# SwitchBoard_MP3_40.net
KiCad netlist of a schematic drawn in EAGLE
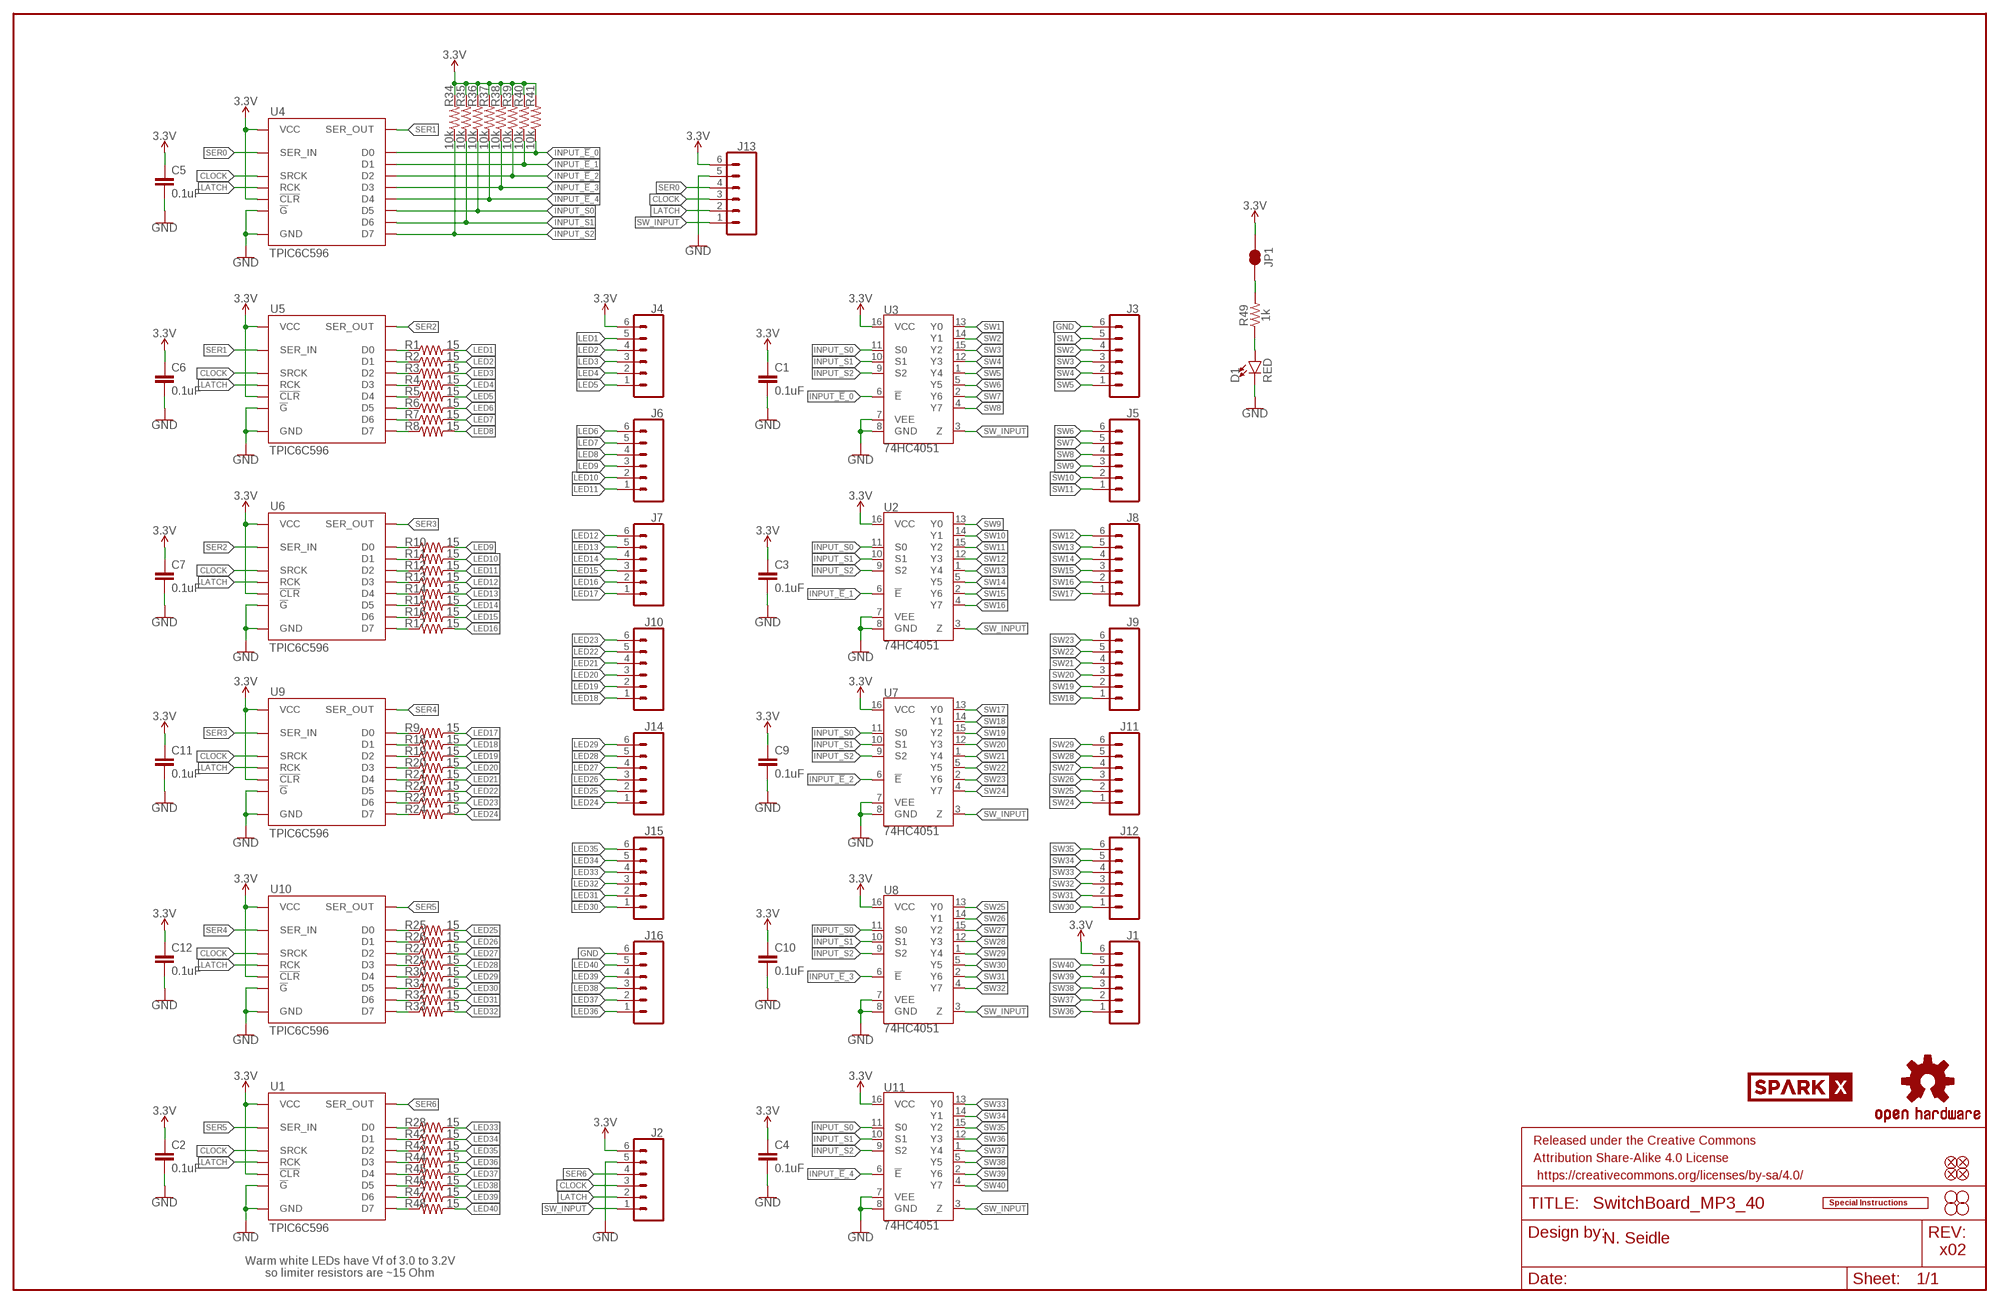
[diagram p0: schematic, sheet 1]

(export (version "E")
  (design (tool "Eeschema 10.0.6"))
  (components
    (comp (ref "C1")
      (value "0.1uF")
      (footprint "eagle-import:0603")
      (libsource (lib "eagle-import") (part "0.1UF-0603-25V-10%-X7R-WE"))
    )
    (comp (ref "C2")
      (value "0.1uF")
      (footprint "eagle-import:0603")
      (libsource (lib "eagle-import") (part "0.1UF-0603-25V-10%-X7R-WE"))
    )
    (comp (ref "C3")
      (value "0.1uF")
      (footprint "eagle-import:0603")
      (libsource (lib "eagle-import") (part "0.1UF-0603-25V-10%-X7R-WE"))
    )
    (comp (ref "C4")
      (value "0.1uF")
      (footprint "eagle-import:0603")
      (libsource (lib "eagle-import") (part "0.1UF-0603-25V-10%-X7R-WE"))
    )
    (comp (ref "C5")
      (value "0.1uF")
      (footprint "eagle-import:0603")
      (libsource (lib "eagle-import") (part "0.1UF-0603-25V-10%-X7R-WE"))
    )
    (comp (ref "C6")
      (value "0.1uF")
      (footprint "eagle-import:0603")
      (libsource (lib "eagle-import") (part "0.1UF-0603-25V-10%-X7R-WE"))
    )
    (comp (ref "C7")
      (value "0.1uF")
      (footprint "eagle-import:0603")
      (libsource (lib "eagle-import") (part "0.1UF-0603-25V-10%-X7R-WE"))
    )
    (comp (ref "C9")
      (value "0.1uF")
      (footprint "eagle-import:0603")
      (libsource (lib "eagle-import") (part "0.1UF-0603-25V-10%-X7R-WE"))
    )
    (comp (ref "C10")
      (value "0.1uF")
      (footprint "eagle-import:0603")
      (libsource (lib "eagle-import") (part "0.1UF-0603-25V-10%-X7R-WE"))
    )
    (comp (ref "C11")
      (value "0.1uF")
      (footprint "eagle-import:0603")
      (libsource (lib "eagle-import") (part "0.1UF-0603-25V-10%-X7R-WE"))
    )
    (comp (ref "C12")
      (value "0.1uF")
      (footprint "eagle-import:0603")
      (libsource (lib "eagle-import") (part "0.1UF-0603-25V-10%-X7R-WE"))
    )
    (comp (ref "D1")
      (value "RED")
      (footprint "eagle-import:LED-0603")
      (libsource (lib "eagle-import") (part "LED-RED0603"))
    )
    (comp (ref "FD1")
      (value "FIDUCIAL1X2")
      (footprint "eagle-import:FIDUCIAL-1X2")
      (libsource (lib "eagle-import") (part "FIDUCIAL1X2"))
    )
    (comp (ref "FD2")
      (value "FIDUCIAL1X2")
      (footprint "eagle-import:FIDUCIAL-1X2")
      (libsource (lib "eagle-import") (part "FIDUCIAL1X2"))
    )
    (comp (ref "FD3")
      (value "FIDUCIAL1X2")
      (footprint "eagle-import:FIDUCIAL-1X2")
      (libsource (lib "eagle-import") (part "FIDUCIAL1X2"))
    )
    (comp (ref "FD4")
      (value "FIDUCIAL1X2")
      (footprint "eagle-import:FIDUCIAL-1X2")
      (libsource (lib "eagle-import") (part "FIDUCIAL1X2"))
    )
    (comp (ref "FRAME2")
      (value "FRAME-LEDGER")
      (footprint "eagle-import:CREATIVE_COMMONS")
      (libsource (lib "eagle-import") (part "FRAME-LEDGER"))
    )
    (comp (ref "H1")
      (value "STAND-OFF")
      (footprint "eagle-import:STAND-OFF")
      (libsource (lib "eagle-import") (part "STAND-OFF"))
    )
    (comp (ref "H2")
      (value "STAND-OFF")
      (footprint "eagle-import:STAND-OFF")
      (libsource (lib "eagle-import") (part "STAND-OFF"))
    )
    (comp (ref "H3")
      (value "STAND-OFF")
      (footprint "eagle-import:STAND-OFF")
      (libsource (lib "eagle-import") (part "STAND-OFF"))
    )
    (comp (ref "H4")
      (value "STAND-OFF")
      (footprint "eagle-import:STAND-OFF")
      (libsource (lib "eagle-import") (part "STAND-OFF"))
    )
    (comp (ref "J1")
      (value "CONN_06JST-SMD-LOCKING")
      (footprint "eagle-import:JST-6-SMD-1.25MM-LOCKING")
      (libsource (lib "eagle-import") (part "CONN_06JST-SMD-LOCKING"))
    )
    (comp (ref "J2")
      (value "CONN_06JST-SMD-LOCKING")
      (footprint "eagle-import:JST-6-SMD-1.25MM-LOCKING")
      (libsource (lib "eagle-import") (part "CONN_06JST-SMD-LOCKING"))
    )
    (comp (ref "J3")
      (value "CONN_06JST-SMD-LOCKING")
      (footprint "eagle-import:JST-6-SMD-1.25MM-LOCKING")
      (libsource (lib "eagle-import") (part "CONN_06JST-SMD-LOCKING"))
    )
    (comp (ref "J4")
      (value "CONN_06JST-SMD-LOCKING")
      (footprint "eagle-import:JST-6-SMD-1.25MM-LOCKING")
      (libsource (lib "eagle-import") (part "CONN_06JST-SMD-LOCKING"))
    )
    (comp (ref "J5")
      (value "CONN_06JST-SMD-LOCKING")
      (footprint "eagle-import:JST-6-SMD-1.25MM-LOCKING")
      (libsource (lib "eagle-import") (part "CONN_06JST-SMD-LOCKING"))
    )
    (comp (ref "J6")
      (value "CONN_06JST-SMD-LOCKING")
      (footprint "eagle-import:JST-6-SMD-1.25MM-LOCKING")
      (libsource (lib "eagle-import") (part "CONN_06JST-SMD-LOCKING"))
    )
    (comp (ref "J7")
      (value "CONN_06JST-SMD-LOCKING")
      (footprint "eagle-import:JST-6-SMD-1.25MM-LOCKING")
      (libsource (lib "eagle-import") (part "CONN_06JST-SMD-LOCKING"))
    )
    (comp (ref "J8")
      (value "CONN_06JST-SMD-LOCKING")
      (footprint "eagle-import:JST-6-SMD-1.25MM-LOCKING")
      (libsource (lib "eagle-import") (part "CONN_06JST-SMD-LOCKING"))
    )
    (comp (ref "J9")
      (value "CONN_06JST-SMD-LOCKING")
      (footprint "eagle-import:JST-6-SMD-1.25MM-LOCKING")
      (libsource (lib "eagle-import") (part "CONN_06JST-SMD-LOCKING"))
    )
    (comp (ref "J10")
      (value "CONN_06JST-SMD-LOCKING")
      (footprint "eagle-import:JST-6-SMD-1.25MM-LOCKING")
      (libsource (lib "eagle-import") (part "CONN_06JST-SMD-LOCKING"))
    )
    (comp (ref "J11")
      (value "CONN_06JST-SMD-LOCKING")
      (footprint "eagle-import:JST-6-SMD-1.25MM-LOCKING")
      (libsource (lib "eagle-import") (part "CONN_06JST-SMD-LOCKING"))
    )
    (comp (ref "J12")
      (value "CONN_06JST-SMD-LOCKING")
      (footprint "eagle-import:JST-6-SMD-1.25MM-LOCKING")
      (libsource (lib "eagle-import") (part "CONN_06JST-SMD-LOCKING"))
    )
    (comp (ref "J13")
      (value "CONN_06JST-SMD-LOCKING")
      (footprint "eagle-import:JST-6-SMD-1.25MM-LOCKING")
      (libsource (lib "eagle-import") (part "CONN_06JST-SMD-LOCKING"))
    )
    (comp (ref "J14")
      (value "CONN_06JST-SMD-LOCKING")
      (footprint "eagle-import:JST-6-SMD-1.25MM-LOCKING")
      (libsource (lib "eagle-import") (part "CONN_06JST-SMD-LOCKING"))
    )
    (comp (ref "J15")
      (value "CONN_06JST-SMD-LOCKING")
      (footprint "eagle-import:JST-6-SMD-1.25MM-LOCKING")
      (libsource (lib "eagle-import") (part "CONN_06JST-SMD-LOCKING"))
    )
    (comp (ref "J16")
      (value "CONN_06JST-SMD-LOCKING")
      (footprint "eagle-import:JST-6-SMD-1.25MM-LOCKING")
      (libsource (lib "eagle-import") (part "CONN_06JST-SMD-LOCKING"))
    )
    (comp (ref "JP1")
      (value "JUMPER-SMT_2_NC_TRACE_SILK")
      (footprint "eagle-import:SMT-JUMPER_2_NC_TRACE_SILK")
      (libsource (lib "eagle-import") (part "JUMPER-SMT_2_NC_TRACE_SILK"))
    )
    (comp (ref "LOGO1")
      (value "SPECIAL_INSTRUCTIONS-ORDERING")
      (footprint "eagle-import:ORDERING_INSTRUCTIONS")
      (libsource (lib "eagle-import") (part "SPECIAL_INSTRUCTIONS-ORDERING"))
    )
    (comp (ref "LOGO2")
      (value "OSHW-LOGOS")
      (footprint "eagle-import:OSHW-LOGO-S")
      (libsource (lib "eagle-import") (part "OSHW-LOGOS"))
    )
    (comp (ref "R1")
      (value "15")
      (footprint "eagle-import:0603")
      (libsource (lib "eagle-import") (part "15OHM-0603-1/10W-1%"))
    )
    (comp (ref "R2")
      (value "15")
      (footprint "eagle-import:0603")
      (libsource (lib "eagle-import") (part "15OHM-0603-1/10W-1%"))
    )
    (comp (ref "R3")
      (value "15")
      (footprint "eagle-import:0603")
      (libsource (lib "eagle-import") (part "15OHM-0603-1/10W-1%"))
    )
    (comp (ref "R4")
      (value "15")
      (footprint "eagle-import:0603")
      (libsource (lib "eagle-import") (part "15OHM-0603-1/10W-1%"))
    )
    (comp (ref "R5")
      (value "15")
      (footprint "eagle-import:0603")
      (libsource (lib "eagle-import") (part "15OHM-0603-1/10W-1%"))
    )
    (comp (ref "R6")
      (value "15")
      (footprint "eagle-import:0603")
      (libsource (lib "eagle-import") (part "15OHM-0603-1/10W-1%"))
    )
    (comp (ref "R7")
      (value "15")
      (footprint "eagle-import:0603")
      (libsource (lib "eagle-import") (part "15OHM-0603-1/10W-1%"))
    )
    (comp (ref "R8")
      (value "15")
      (footprint "eagle-import:0603")
      (libsource (lib "eagle-import") (part "15OHM-0603-1/10W-1%"))
    )
    (comp (ref "R9")
      (value "15")
      (footprint "eagle-import:0603")
      (libsource (lib "eagle-import") (part "15OHM-0603-1/10W-1%"))
    )
    (comp (ref "R10")
      (value "15")
      (footprint "eagle-import:0603")
      (libsource (lib "eagle-import") (part "15OHM-0603-1/10W-1%"))
    )
    (comp (ref "R11")
      (value "15")
      (footprint "eagle-import:0603")
      (libsource (lib "eagle-import") (part "15OHM-0603-1/10W-1%"))
    )
    (comp (ref "R12")
      (value "15")
      (footprint "eagle-import:0603")
      (libsource (lib "eagle-import") (part "15OHM-0603-1/10W-1%"))
    )
    (comp (ref "R13")
      (value "15")
      (footprint "eagle-import:0603")
      (libsource (lib "eagle-import") (part "15OHM-0603-1/10W-1%"))
    )
    (comp (ref "R14")
      (value "15")
      (footprint "eagle-import:0603")
      (libsource (lib "eagle-import") (part "15OHM-0603-1/10W-1%"))
    )
    (comp (ref "R15")
      (value "15")
      (footprint "eagle-import:0603")
      (libsource (lib "eagle-import") (part "15OHM-0603-1/10W-1%"))
    )
    (comp (ref "R16")
      (value "15")
      (footprint "eagle-import:0603")
      (libsource (lib "eagle-import") (part "15OHM-0603-1/10W-1%"))
    )
    (comp (ref "R17")
      (value "15")
      (footprint "eagle-import:0603")
      (libsource (lib "eagle-import") (part "15OHM-0603-1/10W-1%"))
    )
    (comp (ref "R18")
      (value "15")
      (footprint "eagle-import:0603")
      (libsource (lib "eagle-import") (part "15OHM-0603-1/10W-1%"))
    )
    (comp (ref "R19")
      (value "15")
      (footprint "eagle-import:0603")
      (libsource (lib "eagle-import") (part "15OHM-0603-1/10W-1%"))
    )
    (comp (ref "R20")
      (value "15")
      (footprint "eagle-import:0603")
      (libsource (lib "eagle-import") (part "15OHM-0603-1/10W-1%"))
    )
    (comp (ref "R21")
      (value "15")
      (footprint "eagle-import:0603")
      (libsource (lib "eagle-import") (part "15OHM-0603-1/10W-1%"))
    )
    (comp (ref "R22")
      (value "15")
      (footprint "eagle-import:0603")
      (libsource (lib "eagle-import") (part "15OHM-0603-1/10W-1%"))
    )
    (comp (ref "R23")
      (value "15")
      (footprint "eagle-import:0603")
      (libsource (lib "eagle-import") (part "15OHM-0603-1/10W-1%"))
    )
    (comp (ref "R24")
      (value "15")
      (footprint "eagle-import:0603")
      (libsource (lib "eagle-import") (part "15OHM-0603-1/10W-1%"))
    )
    (comp (ref "R25")
      (value "15")
      (footprint "eagle-import:0603")
      (libsource (lib "eagle-import") (part "15OHM-0603-1/10W-1%"))
    )
    (comp (ref "R26")
      (value "15")
      (footprint "eagle-import:0603")
      (libsource (lib "eagle-import") (part "15OHM-0603-1/10W-1%"))
    )
    (comp (ref "R27")
      (value "15")
      (footprint "eagle-import:0603")
      (libsource (lib "eagle-import") (part "15OHM-0603-1/10W-1%"))
    )
    (comp (ref "R28")
      (value "15")
      (footprint "eagle-import:0603")
      (libsource (lib "eagle-import") (part "15OHM-0603-1/10W-1%"))
    )
    (comp (ref "R29")
      (value "15")
      (footprint "eagle-import:0603")
      (libsource (lib "eagle-import") (part "15OHM-0603-1/10W-1%"))
    )
    (comp (ref "R30")
      (value "15")
      (footprint "eagle-import:0603")
      (libsource (lib "eagle-import") (part "15OHM-0603-1/10W-1%"))
    )
    (comp (ref "R31")
      (value "15")
      (footprint "eagle-import:0603")
      (libsource (lib "eagle-import") (part "15OHM-0603-1/10W-1%"))
    )
    (comp (ref "R32")
      (value "15")
      (footprint "eagle-import:0603")
      (libsource (lib "eagle-import") (part "15OHM-0603-1/10W-1%"))
    )
    (comp (ref "R33")
      (value "15")
      (footprint "eagle-import:0603")
      (libsource (lib "eagle-import") (part "15OHM-0603-1/10W-1%"))
    )
    (comp (ref "R34")
      (value "10k")
      (footprint "eagle-import:0603")
      (libsource (lib "eagle-import") (part "10KOHM-0603-1/10W-1%"))
    )
    (comp (ref "R35")
      (value "10k")
      (footprint "eagle-import:0603")
      (libsource (lib "eagle-import") (part "10KOHM-0603-1/10W-1%"))
    )
    (comp (ref "R36")
      (value "10k")
      (footprint "eagle-import:0603")
      (libsource (lib "eagle-import") (part "10KOHM-0603-1/10W-1%"))
    )
    (comp (ref "R37")
      (value "10k")
      (footprint "eagle-import:0603")
      (libsource (lib "eagle-import") (part "10KOHM-0603-1/10W-1%"))
    )
    (comp (ref "R38")
      (value "10k")
      (footprint "eagle-import:0603")
      (libsource (lib "eagle-import") (part "10KOHM-0603-1/10W-1%"))
    )
    (comp (ref "R39")
      (value "10k")
      (footprint "eagle-import:0603")
      (libsource (lib "eagle-import") (part "10KOHM-0603-1/10W-1%"))
    )
    (comp (ref "R40")
      (value "10k")
      (footprint "eagle-import:0603")
      (libsource (lib "eagle-import") (part "10KOHM-0603-1/10W-1%"))
    )
    (comp (ref "R41")
      (value "10k")
      (footprint "eagle-import:0603")
      (libsource (lib "eagle-import") (part "10KOHM-0603-1/10W-1%"))
    )
    (comp (ref "R42")
      (value "15")
      (footprint "eagle-import:0603")
      (libsource (lib "eagle-import") (part "15OHM-0603-1/10W-1%"))
    )
    (comp (ref "R43")
      (value "15")
      (footprint "eagle-import:0603")
      (libsource (lib "eagle-import") (part "15OHM-0603-1/10W-1%"))
    )
    (comp (ref "R44")
      (value "15")
      (footprint "eagle-import:0603")
      (libsource (lib "eagle-import") (part "15OHM-0603-1/10W-1%"))
    )
    (comp (ref "R45")
      (value "15")
      (footprint "eagle-import:0603")
      (libsource (lib "eagle-import") (part "15OHM-0603-1/10W-1%"))
    )
    (comp (ref "R46")
      (value "15")
      (footprint "eagle-import:0603")
      (libsource (lib "eagle-import") (part "15OHM-0603-1/10W-1%"))
    )
    (comp (ref "R47")
      (value "15")
      (footprint "eagle-import:0603")
      (libsource (lib "eagle-import") (part "15OHM-0603-1/10W-1%"))
    )
    (comp (ref "R48")
      (value "15")
      (footprint "eagle-import:0603")
      (libsource (lib "eagle-import") (part "15OHM-0603-1/10W-1%"))
    )
    (comp (ref "R49")
      (value "1k")
      (footprint "eagle-import:0603")
      (libsource (lib "eagle-import") (part "1KOHM-0603-1/10W-1%"))
    )
    (comp (ref "U$1")
      (value "SPARKX-LOGO4")
      (footprint "eagle-import:SPARKX-MEDIUM")
      (libsource (lib "eagle-import") (part "SPARKX-LOGO4"))
    )
    (comp (ref "U1")
      (value "TPIC6C596")
      (footprint "eagle-import:SO016")
      (libsource (lib "eagle-import") (part "TPIC6C596SOIC"))
    )
    (comp (ref "U2")
      (value "74HC4051")
      (footprint "eagle-import:SO16")
      (libsource (lib "eagle-import") (part "744051"))
    )
    (comp (ref "U3")
      (value "74HC4051")
      (footprint "eagle-import:SO16")
      (libsource (lib "eagle-import") (part "744051"))
    )
    (comp (ref "U4")
      (value "TPIC6C596")
      (footprint "eagle-import:SO016")
      (libsource (lib "eagle-import") (part "TPIC6C596SOIC"))
    )
    (comp (ref "U5")
      (value "TPIC6C596")
      (footprint "eagle-import:SO016")
      (libsource (lib "eagle-import") (part "TPIC6C596SOIC"))
    )
    (comp (ref "U6")
      (value "TPIC6C596")
      (footprint "eagle-import:SO016")
      (libsource (lib "eagle-import") (part "TPIC6C596SOIC"))
    )
    (comp (ref "U7")
      (value "74HC4051")
      (footprint "eagle-import:SO16")
      (libsource (lib "eagle-import") (part "744051"))
    )
    (comp (ref "U8")
      (value "74HC4051")
      (footprint "eagle-import:SO16")
      (libsource (lib "eagle-import") (part "744051"))
    )
    (comp (ref "U9")
      (value "TPIC6C596")
      (footprint "eagle-import:SO016")
      (libsource (lib "eagle-import") (part "TPIC6C596SOIC"))
    )
    (comp (ref "U10")
      (value "TPIC6C596")
      (footprint "eagle-import:SO016")
      (libsource (lib "eagle-import") (part "TPIC6C596SOIC"))
    )
    (comp (ref "U11")
      (value "74HC4051")
      (footprint "eagle-import:SO16")
      (libsource (lib "eagle-import") (part "744051"))
    )
  )
  (nets
    (net (code "1") (name "/INPUT_~{E}_0") (class "Default")
      (node (ref "R41") (pin "1") (pinfunction "1_1") (pintype "passive"))
      (node (ref "U3") (pin "6") (pinfunction "~{E}_6") (pintype "bidirectional"))
      (node (ref "U4") (pin "3") (pinfunction "D0_3") (pintype "output"))
    )
    (net (code "2") (name "/INPUT_~{E}_1") (class "Default")
      (node (ref "R40") (pin "1") (pinfunction "1_1") (pintype "passive"))
      (node (ref "U2") (pin "6") (pinfunction "~{E}_6") (pintype "bidirectional"))
      (node (ref "U4") (pin "4") (pinfunction "D1_4") (pintype "output"))
    )
    (net (code "3") (name "/INPUT_~{E}_2") (class "Default")
      (node (ref "R39") (pin "1") (pinfunction "1_1") (pintype "passive"))
      (node (ref "U4") (pin "5") (pinfunction "D2_5") (pintype "output"))
      (node (ref "U7") (pin "6") (pinfunction "~{E}_6") (pintype "bidirectional"))
    )
    (net (code "4") (name "/INPUT_~{E}_3") (class "Default")
      (node (ref "R38") (pin "1") (pinfunction "1_1") (pintype "passive"))
      (node (ref "U4") (pin "6") (pinfunction "D3_6") (pintype "output"))
      (node (ref "U8") (pin "6") (pinfunction "~{E}_6") (pintype "bidirectional"))
    )
    (net (code "5") (name "/INPUT_~{E}_4") (class "Default")
      (node (ref "R37") (pin "1") (pinfunction "1_1") (pintype "passive"))
      (node (ref "U11") (pin "6") (pinfunction "~{E}_6") (pintype "bidirectional"))
      (node (ref "U4") (pin "11") (pinfunction "D4_11") (pintype "output"))
    )
    (net (code "6") (name "3.3V") (class "Default")
      (node (ref "C1") (pin "1") (pinfunction "1_1") (pintype "passive"))
      (node (ref "C10") (pin "1") (pinfunction "1_1") (pintype "passive"))
      (node (ref "C11") (pin "1") (pinfunction "1_1") (pintype "passive"))
      (node (ref "C12") (pin "1") (pinfunction "1_1") (pintype "passive"))
      (node (ref "C2") (pin "1") (pinfunction "1_1") (pintype "passive"))
      (node (ref "C3") (pin "1") (pinfunction "1_1") (pintype "passive"))
      (node (ref "C4") (pin "1") (pinfunction "1_1") (pintype "passive"))
      (node (ref "C5") (pin "1") (pinfunction "1_1") (pintype "passive"))
      (node (ref "C6") (pin "1") (pinfunction "1_1") (pintype "passive"))
      (node (ref "C7") (pin "1") (pinfunction "1_1") (pintype "passive"))
      (node (ref "C9") (pin "1") (pinfunction "1_1") (pintype "passive"))
      (node (ref "J1") (pin "6") (pinfunction "6_6") (pintype "passive"))
      (node (ref "J13") (pin "6") (pinfunction "6_6") (pintype "passive"))
      (node (ref "J2") (pin "6") (pinfunction "6_6") (pintype "passive"))
      (node (ref "J4") (pin "6") (pinfunction "6_6") (pintype "passive"))
      (node (ref "JP1") (pin "2") (pinfunction "2_2") (pintype "passive"))
      (node (ref "R34") (pin "2") (pinfunction "2_2") (pintype "passive"))
      (node (ref "R35") (pin "2") (pinfunction "2_2") (pintype "passive"))
      (node (ref "R36") (pin "2") (pinfunction "2_2") (pintype "passive"))
      (node (ref "R37") (pin "2") (pinfunction "2_2") (pintype "passive"))
      (node (ref "R38") (pin "2") (pinfunction "2_2") (pintype "passive"))
      (node (ref "R39") (pin "2") (pinfunction "2_2") (pintype "passive"))
      (node (ref "R40") (pin "2") (pinfunction "2_2") (pintype "passive"))
      (node (ref "R41") (pin "2") (pinfunction "2_2") (pintype "passive"))
      (node (ref "U1") (pin "1") (pinfunction "VCC_1") (pintype "power_in"))
      (node (ref "U1") (pin "7") (pinfunction "~{CLR}_7") (pintype "input"))
      (node (ref "U10") (pin "1") (pinfunction "VCC_1") (pintype "power_in"))
      (node (ref "U10") (pin "7") (pinfunction "~{CLR}_7") (pintype "input"))
      (node (ref "U11") (pin "16") (pinfunction "VCC_16") (pintype "bidirectional"))
      (node (ref "U2") (pin "16") (pinfunction "VCC_16") (pintype "bidirectional"))
      (node (ref "U3") (pin "16") (pinfunction "VCC_16") (pintype "bidirectional"))
      (node (ref "U4") (pin "1") (pinfunction "VCC_1") (pintype "power_in"))
      (node (ref "U4") (pin "7") (pinfunction "~{CLR}_7") (pintype "input"))
      (node (ref "U5") (pin "1") (pinfunction "VCC_1") (pintype "power_in"))
      (node (ref "U5") (pin "7") (pinfunction "~{CLR}_7") (pintype "input"))
      (node (ref "U6") (pin "1") (pinfunction "VCC_1") (pintype "power_in"))
      (node (ref "U6") (pin "7") (pinfunction "~{CLR}_7") (pintype "input"))
      (node (ref "U7") (pin "16") (pinfunction "VCC_16") (pintype "bidirectional"))
      (node (ref "U8") (pin "16") (pinfunction "VCC_16") (pintype "bidirectional"))
      (node (ref "U9") (pin "1") (pinfunction "VCC_1") (pintype "power_in"))
      (node (ref "U9") (pin "7") (pinfunction "~{CLR}_7") (pintype "input"))
    )
    (net (code "7") (name "CLOCK") (class "Default")
      (node (ref "J13") (pin "3") (pinfunction "3_3") (pintype "passive"))
      (node (ref "J2") (pin "3") (pinfunction "3_3") (pintype "passive"))
      (node (ref "U1") (pin "15") (pinfunction "SRCK_15") (pintype "input"))
      (node (ref "U10") (pin "15") (pinfunction "SRCK_15") (pintype "input"))
      (node (ref "U4") (pin "15") (pinfunction "SRCK_15") (pintype "input"))
      (node (ref "U5") (pin "15") (pinfunction "SRCK_15") (pintype "input"))
      (node (ref "U6") (pin "15") (pinfunction "SRCK_15") (pintype "input"))
      (node (ref "U9") (pin "15") (pinfunction "SRCK_15") (pintype "input"))
    )
    (net (code "8") (name "GND") (class "Default")
      (node (ref "C1") (pin "2") (pinfunction "2_2") (pintype "passive"))
      (node (ref "C10") (pin "2") (pinfunction "2_2") (pintype "passive"))
      (node (ref "C11") (pin "2") (pinfunction "2_2") (pintype "passive"))
      (node (ref "C12") (pin "2") (pinfunction "2_2") (pintype "passive"))
      (node (ref "C2") (pin "2") (pinfunction "2_2") (pintype "passive"))
      (node (ref "C3") (pin "2") (pinfunction "2_2") (pintype "passive"))
      (node (ref "C4") (pin "2") (pinfunction "2_2") (pintype "passive"))
      (node (ref "C5") (pin "2") (pinfunction "2_2") (pintype "passive"))
      (node (ref "C6") (pin "2") (pinfunction "2_2") (pintype "passive"))
      (node (ref "C7") (pin "2") (pinfunction "2_2") (pintype "passive"))
      (node (ref "C9") (pin "2") (pinfunction "2_2") (pintype "passive"))
      (node (ref "D1") (pin "C") (pinfunction "C_C") (pintype "passive"))
      (node (ref "J13") (pin "5") (pinfunction "5_5") (pintype "passive"))
      (node (ref "J16") (pin "6") (pinfunction "6_6") (pintype "passive"))
      (node (ref "J2") (pin "5") (pinfunction "5_5") (pintype "passive"))
      (node (ref "J3") (pin "6") (pinfunction "6_6") (pintype "passive"))
      (node (ref "U1") (pin "16") (pinfunction "GND_16") (pintype "power_in"))
      (node (ref "U1") (pin "8") (pinfunction "~{G}_8") (pintype "input"))
      (node (ref "U10") (pin "16") (pinfunction "GND_16") (pintype "power_in"))
      (node (ref "U10") (pin "8") (pinfunction "~{G}_8") (pintype "input"))
      (node (ref "U11") (pin "7") (pinfunction "VEE_7") (pintype "bidirectional"))
      (node (ref "U11") (pin "8") (pinfunction "GND_8") (pintype "bidirectional"))
      (node (ref "U2") (pin "7") (pinfunction "VEE_7") (pintype "bidirectional"))
      (node (ref "U2") (pin "8") (pinfunction "GND_8") (pintype "bidirectional"))
      (node (ref "U3") (pin "7") (pinfunction "VEE_7") (pintype "bidirectional"))
      (node (ref "U3") (pin "8") (pinfunction "GND_8") (pintype "bidirectional"))
      (node (ref "U4") (pin "16") (pinfunction "GND_16") (pintype "power_in"))
      (node (ref "U4") (pin "8") (pinfunction "~{G}_8") (pintype "input"))
      (node (ref "U5") (pin "16") (pinfunction "GND_16") (pintype "power_in"))
      (node (ref "U5") (pin "8") (pinfunction "~{G}_8") (pintype "input"))
      (node (ref "U6") (pin "16") (pinfunction "GND_16") (pintype "power_in"))
      (node (ref "U6") (pin "8") (pinfunction "~{G}_8") (pintype "input"))
      (node (ref "U7") (pin "7") (pinfunction "VEE_7") (pintype "bidirectional"))
      (node (ref "U7") (pin "8") (pinfunction "GND_8") (pintype "bidirectional"))
      (node (ref "U8") (pin "7") (pinfunction "VEE_7") (pintype "bidirectional"))
      (node (ref "U8") (pin "8") (pinfunction "GND_8") (pintype "bidirectional"))
      (node (ref "U9") (pin "16") (pinfunction "GND_16") (pintype "power_in"))
      (node (ref "U9") (pin "8") (pinfunction "~{G}_8") (pintype "input"))
    )
    (net (code "9") (name "INPUT_S0") (class "Default")
      (node (ref "R36") (pin "1") (pinfunction "1_1") (pintype "passive"))
      (node (ref "U11") (pin "11") (pinfunction "S0_11") (pintype "bidirectional"))
      (node (ref "U2") (pin "11") (pinfunction "S0_11") (pintype "bidirectional"))
      (node (ref "U3") (pin "11") (pinfunction "S0_11") (pintype "bidirectional"))
      (node (ref "U4") (pin "12") (pinfunction "D5_12") (pintype "output"))
      (node (ref "U7") (pin "11") (pinfunction "S0_11") (pintype "bidirectional"))
      (node (ref "U8") (pin "11") (pinfunction "S0_11") (pintype "bidirectional"))
    )
    (net (code "10") (name "INPUT_S1") (class "Default")
      (node (ref "R35") (pin "1") (pinfunction "1_1") (pintype "passive"))
      (node (ref "U11") (pin "10") (pinfunction "S1_10") (pintype "bidirectional"))
      (node (ref "U2") (pin "10") (pinfunction "S1_10") (pintype "bidirectional"))
      (node (ref "U3") (pin "10") (pinfunction "S1_10") (pintype "bidirectional"))
      (node (ref "U4") (pin "13") (pinfunction "D6_13") (pintype "output"))
      (node (ref "U7") (pin "10") (pinfunction "S1_10") (pintype "bidirectional"))
      (node (ref "U8") (pin "10") (pinfunction "S1_10") (pintype "bidirectional"))
    )
    (net (code "11") (name "INPUT_S2") (class "Default")
      (node (ref "R34") (pin "1") (pinfunction "1_1") (pintype "passive"))
      (node (ref "U11") (pin "9") (pinfunction "S2_9") (pintype "bidirectional"))
      (node (ref "U2") (pin "9") (pinfunction "S2_9") (pintype "bidirectional"))
      (node (ref "U3") (pin "9") (pinfunction "S2_9") (pintype "bidirectional"))
      (node (ref "U4") (pin "14") (pinfunction "D7_14") (pintype "output"))
      (node (ref "U7") (pin "9") (pinfunction "S2_9") (pintype "bidirectional"))
      (node (ref "U8") (pin "9") (pinfunction "S2_9") (pintype "bidirectional"))
    )
    (net (code "12") (name "LATCH") (class "Default")
      (node (ref "J13") (pin "2") (pinfunction "2_2") (pintype "passive"))
      (node (ref "J2") (pin "2") (pinfunction "2_2") (pintype "passive"))
      (node (ref "U1") (pin "10") (pinfunction "RCK_10") (pintype "input"))
      (node (ref "U10") (pin "10") (pinfunction "RCK_10") (pintype "input"))
      (node (ref "U4") (pin "10") (pinfunction "RCK_10") (pintype "input"))
      (node (ref "U5") (pin "10") (pinfunction "RCK_10") (pintype "input"))
      (node (ref "U6") (pin "10") (pinfunction "RCK_10") (pintype "input"))
      (node (ref "U9") (pin "10") (pinfunction "RCK_10") (pintype "input"))
    )
    (net (code "13") (name "LED1") (class "Default")
      (node (ref "J4") (pin "5") (pinfunction "5_5") (pintype "passive"))
      (node (ref "R1") (pin "2") (pinfunction "2_2") (pintype "passive"))
    )
    (net (code "14") (name "LED2") (class "Default")
      (node (ref "J4") (pin "4") (pinfunction "4_4") (pintype "passive"))
      (node (ref "R2") (pin "2") (pinfunction "2_2") (pintype "passive"))
    )
    (net (code "15") (name "LED3") (class "Default")
      (node (ref "J4") (pin "3") (pinfunction "3_3") (pintype "passive"))
      (node (ref "R3") (pin "2") (pinfunction "2_2") (pintype "passive"))
    )
    (net (code "16") (name "LED4") (class "Default")
      (node (ref "J4") (pin "2") (pinfunction "2_2") (pintype "passive"))
      (node (ref "R4") (pin "2") (pinfunction "2_2") (pintype "passive"))
    )
    (net (code "17") (name "LED5") (class "Default")
      (node (ref "J4") (pin "1") (pinfunction "1_1") (pintype "passive"))
      (node (ref "R5") (pin "2") (pinfunction "2_2") (pintype "passive"))
    )
    (net (code "18") (name "LED6") (class "Default")
      (node (ref "J6") (pin "6") (pinfunction "6_6") (pintype "passive"))
      (node (ref "R6") (pin "2") (pinfunction "2_2") (pintype "passive"))
    )
    (net (code "19") (name "LED7") (class "Default")
      (node (ref "J6") (pin "5") (pinfunction "5_5") (pintype "passive"))
      (node (ref "R7") (pin "2") (pinfunction "2_2") (pintype "passive"))
    )
    (net (code "20") (name "LED8") (class "Default")
      (node (ref "J6") (pin "4") (pinfunction "4_4") (pintype "passive"))
      (node (ref "R8") (pin "2") (pinfunction "2_2") (pintype "passive"))
    )
    (net (code "21") (name "LED9") (class "Default")
      (node (ref "J6") (pin "3") (pinfunction "3_3") (pintype "passive"))
      (node (ref "R10") (pin "2") (pinfunction "2_2") (pintype "passive"))
    )
    (net (code "22") (name "LED10") (class "Default")
      (node (ref "J6") (pin "2") (pinfunction "2_2") (pintype "passive"))
      (node (ref "R11") (pin "2") (pinfunction "2_2") (pintype "passive"))
    )
    (net (code "23") (name "LED11") (class "Default")
      (node (ref "J6") (pin "1") (pinfunction "1_1") (pintype "passive"))
      (node (ref "R12") (pin "2") (pinfunction "2_2") (pintype "passive"))
    )
    (net (code "24") (name "LED12") (class "Default")
      (node (ref "J7") (pin "6") (pinfunction "6_6") (pintype "passive"))
      (node (ref "R13") (pin "2") (pinfunction "2_2") (pintype "passive"))
    )
    (net (code "25") (name "LED13") (class "Default")
      (node (ref "J7") (pin "5") (pinfunction "5_5") (pintype "passive"))
      (node (ref "R14") (pin "2") (pinfunction "2_2") (pintype "passive"))
    )
    (net (code "26") (name "LED14") (class "Default")
      (node (ref "J7") (pin "4") (pinfunction "4_4") (pintype "passive"))
      (node (ref "R15") (pin "2") (pinfunction "2_2") (pintype "passive"))
    )
    (net (code "27") (name "LED15") (class "Default")
      (node (ref "J7") (pin "3") (pinfunction "3_3") (pintype "passive"))
      (node (ref "R16") (pin "2") (pinfunction "2_2") (pintype "passive"))
    )
    (net (code "28") (name "LED16") (class "Default")
      (node (ref "J7") (pin "2") (pinfunction "2_2") (pintype "passive"))
      (node (ref "R17") (pin "2") (pinfunction "2_2") (pintype "passive"))
    )
    (net (code "29") (name "LED17") (class "Default")
      (node (ref "J7") (pin "1") (pinfunction "1_1") (pintype "passive"))
      (node (ref "R9") (pin "2") (pinfunction "2_2") (pintype "passive"))
    )
    (net (code "30") (name "LED18") (class "Default")
      (node (ref "J10") (pin "1") (pinfunction "1_1") (pintype "passive"))
      (node (ref "R18") (pin "2") (pinfunction "2_2") (pintype "passive"))
    )
    (net (code "31") (name "LED19") (class "Default")
      (node (ref "J10") (pin "2") (pinfunction "2_2") (pintype "passive"))
      (node (ref "R19") (pin "2") (pinfunction "2_2") (pintype "passive"))
    )
    (net (code "32") (name "LED20") (class "Default")
      (node (ref "J10") (pin "3") (pinfunction "3_3") (pintype "passive"))
      (node (ref "R20") (pin "2") (pinfunction "2_2") (pintype "passive"))
    )
    (net (code "33") (name "LED21") (class "Default")
      (node (ref "J10") (pin "4") (pinfunction "4_4") (pintype "passive"))
      (node (ref "R21") (pin "2") (pinfunction "2_2") (pintype "passive"))
    )
    (net (code "34") (name "LED22") (class "Default")
      (node (ref "J10") (pin "5") (pinfunction "5_5") (pintype "passive"))
      (node (ref "R22") (pin "2") (pinfunction "2_2") (pintype "passive"))
    )
    (net (code "35") (name "LED23") (class "Default")
      (node (ref "J10") (pin "6") (pinfunction "6_6") (pintype "passive"))
      (node (ref "R23") (pin "2") (pinfunction "2_2") (pintype "passive"))
    )
    (net (code "36") (name "LED24") (class "Default")
      (node (ref "J14") (pin "1") (pinfunction "1_1") (pintype "passive"))
      (node (ref "R24") (pin "2") (pinfunction "2_2") (pintype "passive"))
    )
    (net (code "37") (name "LED25") (class "Default")
      (node (ref "J14") (pin "2") (pinfunction "2_2") (pintype "passive"))
      (node (ref "R25") (pin "2") (pinfunction "2_2") (pintype "passive"))
    )
    (net (code "38") (name "LED26") (class "Default")
      (node (ref "J14") (pin "3") (pinfunction "3_3") (pintype "passive"))
      (node (ref "R26") (pin "2") (pinfunction "2_2") (pintype "passive"))
    )
    (net (code "39") (name "LED27") (class "Default")
      (node (ref "J14") (pin "4") (pinfunction "4_4") (pintype "passive"))
      (node (ref "R27") (pin "2") (pinfunction "2_2") (pintype "passive"))
    )
    (net (code "40") (name "LED28") (class "Default")
      (node (ref "J14") (pin "5") (pinfunction "5_5") (pintype "passive"))
      (node (ref "R29") (pin "2") (pinfunction "2_2") (pintype "passive"))
    )
    (net (code "41") (name "LED29") (class "Default")
      (node (ref "J14") (pin "6") (pinfunction "6_6") (pintype "passive"))
      (node (ref "R30") (pin "2") (pinfunction "2_2") (pintype "passive"))
    )
    (net (code "42") (name "LED30") (class "Default")
      (node (ref "J15") (pin "1") (pinfunction "1_1") (pintype "passive"))
      (node (ref "R31") (pin "2") (pinfunction "2_2") (pintype "passive"))
    )
    (net (code "43") (name "LED31") (class "Default")
      (node (ref "J15") (pin "2") (pinfunction "2_2") (pintype "passive"))
      (node (ref "R32") (pin "2") (pinfunction "2_2") (pintype "passive"))
    )
    (net (code "44") (name "LED32") (class "Default")
      (node (ref "J15") (pin "3") (pinfunction "3_3") (pintype "passive"))
      (node (ref "R33") (pin "2") (pinfunction "2_2") (pintype "passive"))
    )
    (net (code "45") (name "LED33") (class "Default")
      (node (ref "J15") (pin "4") (pinfunction "4_4") (pintype "passive"))
      (node (ref "R28") (pin "2") (pinfunction "2_2") (pintype "passive"))
    )
    (net (code "46") (name "LED34") (class "Default")
      (node (ref "J15") (pin "5") (pinfunction "5_5") (pintype "passive"))
      (node (ref "R42") (pin "2") (pinfunction "2_2") (pintype "passive"))
    )
    (net (code "47") (name "LED35") (class "Default")
      (node (ref "J15") (pin "6") (pinfunction "6_6") (pintype "passive"))
      (node (ref "R43") (pin "2") (pinfunction "2_2") (pintype "passive"))
    )
    (net (code "48") (name "LED36") (class "Default")
      (node (ref "J16") (pin "1") (pinfunction "1_1") (pintype "passive"))
      (node (ref "R44") (pin "2") (pinfunction "2_2") (pintype "passive"))
    )
    (net (code "49") (name "LED37") (class "Default")
      (node (ref "J16") (pin "2") (pinfunction "2_2") (pintype "passive"))
      (node (ref "R45") (pin "2") (pinfunction "2_2") (pintype "passive"))
    )
    (net (code "50") (name "LED38") (class "Default")
      (node (ref "J16") (pin "3") (pinfunction "3_3") (pintype "passive"))
      (node (ref "R46") (pin "2") (pinfunction "2_2") (pintype "passive"))
    )
    (net (code "51") (name "LED39") (class "Default")
      (node (ref "J16") (pin "4") (pinfunction "4_4") (pintype "passive"))
      (node (ref "R47") (pin "2") (pinfunction "2_2") (pintype "passive"))
    )
    (net (code "52") (name "LED40") (class "Default")
      (node (ref "J16") (pin "5") (pinfunction "5_5") (pintype "passive"))
      (node (ref "R48") (pin "2") (pinfunction "2_2") (pintype "passive"))
    )
    (net (code "53") (name "Net-(D1-PadA)") (class "Default")
      (node (ref "D1") (pin "A") (pinfunction "A_A") (pintype "passive"))
      (node (ref "R49") (pin "1") (pinfunction "1_1") (pintype "passive"))
    )
    (net (code "54") (name "Net-(JP1-Pad1)") (class "Default")
      (node (ref "JP1") (pin "1") (pinfunction "1_1") (pintype "passive"))
      (node (ref "R49") (pin "2") (pinfunction "2_2") (pintype "passive"))
    )
    (net (code "55") (name "Net-(U1-D0)") (class "Default")
      (node (ref "R28") (pin "1") (pinfunction "1_1") (pintype "passive"))
      (node (ref "U1") (pin "3") (pinfunction "D0_3") (pintype "output"))
    )
    (net (code "56") (name "Net-(U1-D1)") (class "Default")
      (node (ref "R42") (pin "1") (pinfunction "1_1") (pintype "passive"))
      (node (ref "U1") (pin "4") (pinfunction "D1_4") (pintype "output"))
    )
    (net (code "57") (name "Net-(U1-D2)") (class "Default")
      (node (ref "R43") (pin "1") (pinfunction "1_1") (pintype "passive"))
      (node (ref "U1") (pin "5") (pinfunction "D2_5") (pintype "output"))
    )
    (net (code "58") (name "Net-(U1-D3)") (class "Default")
      (node (ref "R44") (pin "1") (pinfunction "1_1") (pintype "passive"))
      (node (ref "U1") (pin "6") (pinfunction "D3_6") (pintype "output"))
    )
    (net (code "59") (name "Net-(U1-D4)") (class "Default")
      (node (ref "R45") (pin "1") (pinfunction "1_1") (pintype "passive"))
      (node (ref "U1") (pin "11") (pinfunction "D4_11") (pintype "output"))
    )
    (net (code "60") (name "Net-(U1-D5)") (class "Default")
      (node (ref "R46") (pin "1") (pinfunction "1_1") (pintype "passive"))
      (node (ref "U1") (pin "12") (pinfunction "D5_12") (pintype "output"))
    )
    (net (code "61") (name "Net-(U1-D6)") (class "Default")
      (node (ref "R47") (pin "1") (pinfunction "1_1") (pintype "passive"))
      (node (ref "U1") (pin "13") (pinfunction "D6_13") (pintype "output"))
    )
    (net (code "62") (name "Net-(U1-D7)") (class "Default")
      (node (ref "R48") (pin "1") (pinfunction "1_1") (pintype "passive"))
      (node (ref "U1") (pin "14") (pinfunction "D7_14") (pintype "output"))
    )
    (net (code "63") (name "Net-(U5-D0)") (class "Default")
      (node (ref "R1") (pin "1") (pinfunction "1_1") (pintype "passive"))
      (node (ref "U5") (pin "3") (pinfunction "D0_3") (pintype "output"))
    )
    (net (code "64") (name "Net-(U5-D1)") (class "Default")
      (node (ref "R2") (pin "1") (pinfunction "1_1") (pintype "passive"))
      (node (ref "U5") (pin "4") (pinfunction "D1_4") (pintype "output"))
    )
    (net (code "65") (name "Net-(U5-D2)") (class "Default")
      (node (ref "R3") (pin "1") (pinfunction "1_1") (pintype "passive"))
      (node (ref "U5") (pin "5") (pinfunction "D2_5") (pintype "output"))
    )
    (net (code "66") (name "Net-(U5-D3)") (class "Default")
      (node (ref "R4") (pin "1") (pinfunction "1_1") (pintype "passive"))
      (node (ref "U5") (pin "6") (pinfunction "D3_6") (pintype "output"))
    )
    (net (code "67") (name "Net-(U5-D4)") (class "Default")
      (node (ref "R5") (pin "1") (pinfunction "1_1") (pintype "passive"))
      (node (ref "U5") (pin "11") (pinfunction "D4_11") (pintype "output"))
    )
    (net (code "68") (name "Net-(U5-D5)") (class "Default")
      (node (ref "R6") (pin "1") (pinfunction "1_1") (pintype "passive"))
      (node (ref "U5") (pin "12") (pinfunction "D5_12") (pintype "output"))
    )
    (net (code "69") (name "Net-(U5-D6)") (class "Default")
      (node (ref "R7") (pin "1") (pinfunction "1_1") (pintype "passive"))
      (node (ref "U5") (pin "13") (pinfunction "D6_13") (pintype "output"))
    )
    (net (code "70") (name "Net-(U5-D7)") (class "Default")
      (node (ref "R8") (pin "1") (pinfunction "1_1") (pintype "passive"))
      (node (ref "U5") (pin "14") (pinfunction "D7_14") (pintype "output"))
    )
    (net (code "71") (name "Net-(U6-D0)") (class "Default")
      (node (ref "R10") (pin "1") (pinfunction "1_1") (pintype "passive"))
      (node (ref "U6") (pin "3") (pinfunction "D0_3") (pintype "output"))
    )
    (net (code "72") (name "Net-(U6-D1)") (class "Default")
      (node (ref "R11") (pin "1") (pinfunction "1_1") (pintype "passive"))
      (node (ref "U6") (pin "4") (pinfunction "D1_4") (pintype "output"))
    )
    (net (code "73") (name "Net-(U6-D2)") (class "Default")
      (node (ref "R12") (pin "1") (pinfunction "1_1") (pintype "passive"))
      (node (ref "U6") (pin "5") (pinfunction "D2_5") (pintype "output"))
    )
    (net (code "74") (name "Net-(U6-D3)") (class "Default")
      (node (ref "R13") (pin "1") (pinfunction "1_1") (pintype "passive"))
      (node (ref "U6") (pin "6") (pinfunction "D3_6") (pintype "output"))
    )
    (net (code "75") (name "Net-(U6-D4)") (class "Default")
      (node (ref "R14") (pin "1") (pinfunction "1_1") (pintype "passive"))
      (node (ref "U6") (pin "11") (pinfunction "D4_11") (pintype "output"))
    )
    (net (code "76") (name "Net-(U6-D5)") (class "Default")
      (node (ref "R15") (pin "1") (pinfunction "1_1") (pintype "passive"))
      (node (ref "U6") (pin "12") (pinfunction "D5_12") (pintype "output"))
    )
    (net (code "77") (name "Net-(U6-D6)") (class "Default")
      (node (ref "R16") (pin "1") (pinfunction "1_1") (pintype "passive"))
      (node (ref "U6") (pin "13") (pinfunction "D6_13") (pintype "output"))
    )
    (net (code "78") (name "Net-(U6-D7)") (class "Default")
      (node (ref "R17") (pin "1") (pinfunction "1_1") (pintype "passive"))
      (node (ref "U6") (pin "14") (pinfunction "D7_14") (pintype "output"))
    )
    (net (code "79") (name "Net-(U9-D0)") (class "Default")
      (node (ref "R9") (pin "1") (pinfunction "1_1") (pintype "passive"))
      (node (ref "U9") (pin "3") (pinfunction "D0_3") (pintype "output"))
    )
    (net (code "80") (name "Net-(U9-D1)") (class "Default")
      (node (ref "R18") (pin "1") (pinfunction "1_1") (pintype "passive"))
      (node (ref "U9") (pin "4") (pinfunction "D1_4") (pintype "output"))
    )
    (net (code "81") (name "Net-(U9-D2)") (class "Default")
      (node (ref "R19") (pin "1") (pinfunction "1_1") (pintype "passive"))
      (node (ref "U9") (pin "5") (pinfunction "D2_5") (pintype "output"))
    )
    (net (code "82") (name "Net-(U9-D3)") (class "Default")
      (node (ref "R20") (pin "1") (pinfunction "1_1") (pintype "passive"))
      (node (ref "U9") (pin "6") (pinfunction "D3_6") (pintype "output"))
    )
    (net (code "83") (name "Net-(U9-D4)") (class "Default")
      (node (ref "R21") (pin "1") (pinfunction "1_1") (pintype "passive"))
      (node (ref "U9") (pin "11") (pinfunction "D4_11") (pintype "output"))
    )
    (net (code "84") (name "Net-(U9-D5)") (class "Default")
      (node (ref "R22") (pin "1") (pinfunction "1_1") (pintype "passive"))
      (node (ref "U9") (pin "12") (pinfunction "D5_12") (pintype "output"))
    )
    (net (code "85") (name "Net-(U9-D6)") (class "Default")
      (node (ref "R23") (pin "1") (pinfunction "1_1") (pintype "passive"))
      (node (ref "U9") (pin "13") (pinfunction "D6_13") (pintype "output"))
    )
    (net (code "86") (name "Net-(U9-D7)") (class "Default")
      (node (ref "R24") (pin "1") (pinfunction "1_1") (pintype "passive"))
      (node (ref "U9") (pin "14") (pinfunction "D7_14") (pintype "output"))
    )
    (net (code "87") (name "Net-(U10-D0)") (class "Default")
      (node (ref "R25") (pin "1") (pinfunction "1_1") (pintype "passive"))
      (node (ref "U10") (pin "3") (pinfunction "D0_3") (pintype "output"))
    )
    (net (code "88") (name "Net-(U10-D1)") (class "Default")
      (node (ref "R26") (pin "1") (pinfunction "1_1") (pintype "passive"))
      (node (ref "U10") (pin "4") (pinfunction "D1_4") (pintype "output"))
    )
    (net (code "89") (name "Net-(U10-D2)") (class "Default")
      (node (ref "R27") (pin "1") (pinfunction "1_1") (pintype "passive"))
      (node (ref "U10") (pin "5") (pinfunction "D2_5") (pintype "output"))
    )
    (net (code "90") (name "Net-(U10-D3)") (class "Default")
      (node (ref "R29") (pin "1") (pinfunction "1_1") (pintype "passive"))
      (node (ref "U10") (pin "6") (pinfunction "D3_6") (pintype "output"))
    )
    (net (code "91") (name "Net-(U10-D4)") (class "Default")
      (node (ref "R30") (pin "1") (pinfunction "1_1") (pintype "passive"))
      (node (ref "U10") (pin "11") (pinfunction "D4_11") (pintype "output"))
    )
    (net (code "92") (name "Net-(U10-D5)") (class "Default")
      (node (ref "R31") (pin "1") (pinfunction "1_1") (pintype "passive"))
      (node (ref "U10") (pin "12") (pinfunction "D5_12") (pintype "output"))
    )
    (net (code "93") (name "Net-(U10-D6)") (class "Default")
      (node (ref "R32") (pin "1") (pinfunction "1_1") (pintype "passive"))
      (node (ref "U10") (pin "13") (pinfunction "D6_13") (pintype "output"))
    )
    (net (code "94") (name "Net-(U10-D7)") (class "Default")
      (node (ref "R33") (pin "1") (pinfunction "1_1") (pintype "passive"))
      (node (ref "U10") (pin "14") (pinfunction "D7_14") (pintype "output"))
    )
    (net (code "95") (name "SER0") (class "Default")
      (node (ref "J13") (pin "4") (pinfunction "4_4") (pintype "passive"))
      (node (ref "U4") (pin "2") (pinfunction "SER_IN_2") (pintype "input"))
    )
    (net (code "96") (name "SER1") (class "Default")
      (node (ref "U4") (pin "9") (pinfunction "SER_OUT_9") (pintype "output"))
      (node (ref "U5") (pin "2") (pinfunction "SER_IN_2") (pintype "input"))
    )
    (net (code "97") (name "SER2") (class "Default")
      (node (ref "U5") (pin "9") (pinfunction "SER_OUT_9") (pintype "output"))
      (node (ref "U6") (pin "2") (pinfunction "SER_IN_2") (pintype "input"))
    )
    (net (code "98") (name "SER3") (class "Default")
      (node (ref "U6") (pin "9") (pinfunction "SER_OUT_9") (pintype "output"))
      (node (ref "U9") (pin "2") (pinfunction "SER_IN_2") (pintype "input"))
    )
    (net (code "99") (name "SER4") (class "Default")
      (node (ref "U10") (pin "2") (pinfunction "SER_IN_2") (pintype "input"))
      (node (ref "U9") (pin "9") (pinfunction "SER_OUT_9") (pintype "output"))
    )
    (net (code "100") (name "SER5") (class "Default")
      (node (ref "U1") (pin "2") (pinfunction "SER_IN_2") (pintype "input"))
      (node (ref "U10") (pin "9") (pinfunction "SER_OUT_9") (pintype "output"))
    )
    (net (code "101") (name "SER6") (class "Default")
      (node (ref "J2") (pin "4") (pinfunction "4_4") (pintype "passive"))
      (node (ref "U1") (pin "9") (pinfunction "SER_OUT_9") (pintype "output"))
    )
    (net (code "102") (name "SW1") (class "Default")
      (node (ref "J3") (pin "5") (pinfunction "5_5") (pintype "passive"))
      (node (ref "U3") (pin "13") (pinfunction "Y0_13") (pintype "bidirectional"))
    )
    (net (code "103") (name "SW2") (class "Default")
      (node (ref "J3") (pin "4") (pinfunction "4_4") (pintype "passive"))
      (node (ref "U3") (pin "14") (pinfunction "Y1_14") (pintype "bidirectional"))
    )
    (net (code "104") (name "SW3") (class "Default")
      (node (ref "J3") (pin "3") (pinfunction "3_3") (pintype "passive"))
      (node (ref "U3") (pin "15") (pinfunction "Y2_15") (pintype "bidirectional"))
    )
    (net (code "105") (name "SW4") (class "Default")
      (node (ref "J3") (pin "2") (pinfunction "2_2") (pintype "passive"))
      (node (ref "U3") (pin "12") (pinfunction "Y3_12") (pintype "bidirectional"))
    )
    (net (code "106") (name "SW5") (class "Default")
      (node (ref "J3") (pin "1") (pinfunction "1_1") (pintype "passive"))
      (node (ref "U3") (pin "1") (pinfunction "Y4_1") (pintype "bidirectional"))
    )
    (net (code "107") (name "SW6") (class "Default")
      (node (ref "J5") (pin "6") (pinfunction "6_6") (pintype "passive"))
      (node (ref "U3") (pin "5") (pinfunction "Y5_5") (pintype "bidirectional"))
    )
    (net (code "108") (name "SW7") (class "Default")
      (node (ref "J5") (pin "5") (pinfunction "5_5") (pintype "passive"))
      (node (ref "U3") (pin "2") (pinfunction "Y6_2") (pintype "bidirectional"))
    )
    (net (code "109") (name "SW8") (class "Default")
      (node (ref "J5") (pin "4") (pinfunction "4_4") (pintype "passive"))
      (node (ref "U3") (pin "4") (pinfunction "Y7_4") (pintype "bidirectional"))
    )
    (net (code "110") (name "SW9") (class "Default")
      (node (ref "J5") (pin "3") (pinfunction "3_3") (pintype "passive"))
      (node (ref "U2") (pin "13") (pinfunction "Y0_13") (pintype "bidirectional"))
    )
    (net (code "111") (name "SW10") (class "Default")
      (node (ref "J5") (pin "2") (pinfunction "2_2") (pintype "passive"))
      (node (ref "U2") (pin "14") (pinfunction "Y1_14") (pintype "bidirectional"))
    )
    (net (code "112") (name "SW11") (class "Default")
      (node (ref "J5") (pin "1") (pinfunction "1_1") (pintype "passive"))
      (node (ref "U2") (pin "15") (pinfunction "Y2_15") (pintype "bidirectional"))
    )
    (net (code "113") (name "SW12") (class "Default")
      (node (ref "J8") (pin "6") (pinfunction "6_6") (pintype "passive"))
      (node (ref "U2") (pin "12") (pinfunction "Y3_12") (pintype "bidirectional"))
    )
    (net (code "114") (name "SW13") (class "Default")
      (node (ref "J8") (pin "5") (pinfunction "5_5") (pintype "passive"))
      (node (ref "U2") (pin "1") (pinfunction "Y4_1") (pintype "bidirectional"))
    )
    (net (code "115") (name "SW14") (class "Default")
      (node (ref "J8") (pin "4") (pinfunction "4_4") (pintype "passive"))
      (node (ref "U2") (pin "5") (pinfunction "Y5_5") (pintype "bidirectional"))
    )
    (net (code "116") (name "SW15") (class "Default")
      (node (ref "J8") (pin "3") (pinfunction "3_3") (pintype "passive"))
      (node (ref "U2") (pin "2") (pinfunction "Y6_2") (pintype "bidirectional"))
    )
    (net (code "117") (name "SW16") (class "Default")
      (node (ref "J8") (pin "2") (pinfunction "2_2") (pintype "passive"))
      (node (ref "U2") (pin "4") (pinfunction "Y7_4") (pintype "bidirectional"))
    )
    (net (code "118") (name "SW17") (class "Default")
      (node (ref "J8") (pin "1") (pinfunction "1_1") (pintype "passive"))
      (node (ref "U7") (pin "13") (pinfunction "Y0_13") (pintype "bidirectional"))
    )
    (net (code "119") (name "SW18") (class "Default")
      (node (ref "J9") (pin "1") (pinfunction "1_1") (pintype "passive"))
      (node (ref "U7") (pin "14") (pinfunction "Y1_14") (pintype "bidirectional"))
    )
    (net (code "120") (name "SW19") (class "Default")
      (node (ref "J9") (pin "2") (pinfunction "2_2") (pintype "passive"))
      (node (ref "U7") (pin "15") (pinfunction "Y2_15") (pintype "bidirectional"))
    )
    (net (code "121") (name "SW20") (class "Default")
      (node (ref "J9") (pin "3") (pinfunction "3_3") (pintype "passive"))
      (node (ref "U7") (pin "12") (pinfunction "Y3_12") (pintype "bidirectional"))
    )
    (net (code "122") (name "SW21") (class "Default")
      (node (ref "J9") (pin "4") (pinfunction "4_4") (pintype "passive"))
      (node (ref "U7") (pin "1") (pinfunction "Y4_1") (pintype "bidirectional"))
    )
    (net (code "123") (name "SW22") (class "Default")
      (node (ref "J9") (pin "5") (pinfunction "5_5") (pintype "passive"))
      (node (ref "U7") (pin "5") (pinfunction "Y5_5") (pintype "bidirectional"))
    )
    (net (code "124") (name "SW23") (class "Default")
      (node (ref "J9") (pin "6") (pinfunction "6_6") (pintype "passive"))
      (node (ref "U7") (pin "2") (pinfunction "Y6_2") (pintype "bidirectional"))
    )
    (net (code "125") (name "SW24") (class "Default")
      (node (ref "J11") (pin "1") (pinfunction "1_1") (pintype "passive"))
      (node (ref "U7") (pin "4") (pinfunction "Y7_4") (pintype "bidirectional"))
    )
    (net (code "126") (name "SW25") (class "Default")
      (node (ref "J11") (pin "2") (pinfunction "2_2") (pintype "passive"))
      (node (ref "U8") (pin "13") (pinfunction "Y0_13") (pintype "bidirectional"))
    )
    (net (code "127") (name "SW26") (class "Default")
      (node (ref "J11") (pin "3") (pinfunction "3_3") (pintype "passive"))
      (node (ref "U8") (pin "14") (pinfunction "Y1_14") (pintype "bidirectional"))
    )
    (net (code "128") (name "SW27") (class "Default")
      (node (ref "J11") (pin "4") (pinfunction "4_4") (pintype "passive"))
      (node (ref "U8") (pin "15") (pinfunction "Y2_15") (pintype "bidirectional"))
    )
    (net (code "129") (name "SW28") (class "Default")
      (node (ref "J11") (pin "5") (pinfunction "5_5") (pintype "passive"))
      (node (ref "U8") (pin "12") (pinfunction "Y3_12") (pintype "bidirectional"))
    )
    (net (code "130") (name "SW29") (class "Default")
      (node (ref "J11") (pin "6") (pinfunction "6_6") (pintype "passive"))
      (node (ref "U8") (pin "1") (pinfunction "Y4_1") (pintype "bidirectional"))
    )
    (net (code "131") (name "SW30") (class "Default")
      (node (ref "J12") (pin "1") (pinfunction "1_1") (pintype "passive"))
      (node (ref "U8") (pin "5") (pinfunction "Y5_5") (pintype "bidirectional"))
    )
    (net (code "132") (name "SW31") (class "Default")
      (node (ref "J12") (pin "2") (pinfunction "2_2") (pintype "passive"))
      (node (ref "U8") (pin "2") (pinfunction "Y6_2") (pintype "bidirectional"))
    )
    (net (code "133") (name "SW32") (class "Default")
      (node (ref "J12") (pin "3") (pinfunction "3_3") (pintype "passive"))
      (node (ref "U8") (pin "4") (pinfunction "Y7_4") (pintype "bidirectional"))
    )
    (net (code "134") (name "SW33") (class "Default")
      (node (ref "J12") (pin "4") (pinfunction "4_4") (pintype "passive"))
      (node (ref "U11") (pin "13") (pinfunction "Y0_13") (pintype "bidirectional"))
    )
    (net (code "135") (name "SW34") (class "Default")
      (node (ref "J12") (pin "5") (pinfunction "5_5") (pintype "passive"))
      (node (ref "U11") (pin "14") (pinfunction "Y1_14") (pintype "bidirectional"))
    )
    (net (code "136") (name "SW35") (class "Default")
      (node (ref "J12") (pin "6") (pinfunction "6_6") (pintype "passive"))
      (node (ref "U11") (pin "15") (pinfunction "Y2_15") (pintype "bidirectional"))
    )
    (net (code "137") (name "SW36") (class "Default")
      (node (ref "J1") (pin "1") (pinfunction "1_1") (pintype "passive"))
      (node (ref "U11") (pin "12") (pinfunction "Y3_12") (pintype "bidirectional"))
    )
    (net (code "138") (name "SW37") (class "Default")
      (node (ref "J1") (pin "2") (pinfunction "2_2") (pintype "passive"))
      (node (ref "U11") (pin "1") (pinfunction "Y4_1") (pintype "bidirectional"))
    )
    (net (code "139") (name "SW38") (class "Default")
      (node (ref "J1") (pin "3") (pinfunction "3_3") (pintype "passive"))
      (node (ref "U11") (pin "5") (pinfunction "Y5_5") (pintype "bidirectional"))
    )
    (net (code "140") (name "SW39") (class "Default")
      (node (ref "J1") (pin "4") (pinfunction "4_4") (pintype "passive"))
      (node (ref "U11") (pin "2") (pinfunction "Y6_2") (pintype "bidirectional"))
    )
    (net (code "141") (name "SW40") (class "Default")
      (node (ref "J1") (pin "5") (pinfunction "5_5") (pintype "passive"))
      (node (ref "U11") (pin "4") (pinfunction "Y7_4") (pintype "bidirectional"))
    )
    (net (code "142") (name "SW_INPUT") (class "Default")
      (node (ref "J13") (pin "1") (pinfunction "1_1") (pintype "passive"))
      (node (ref "J2") (pin "1") (pinfunction "1_1") (pintype "passive"))
      (node (ref "U11") (pin "3") (pinfunction "Z_3") (pintype "bidirectional"))
      (node (ref "U2") (pin "3") (pinfunction "Z_3") (pintype "bidirectional"))
      (node (ref "U3") (pin "3") (pinfunction "Z_3") (pintype "bidirectional"))
      (node (ref "U7") (pin "3") (pinfunction "Z_3") (pintype "bidirectional"))
      (node (ref "U8") (pin "3") (pinfunction "Z_3") (pintype "bidirectional"))
    )
  )
)
